# ControlDSP.net
KiCad netlist of a schematic drawn in Altium Designer
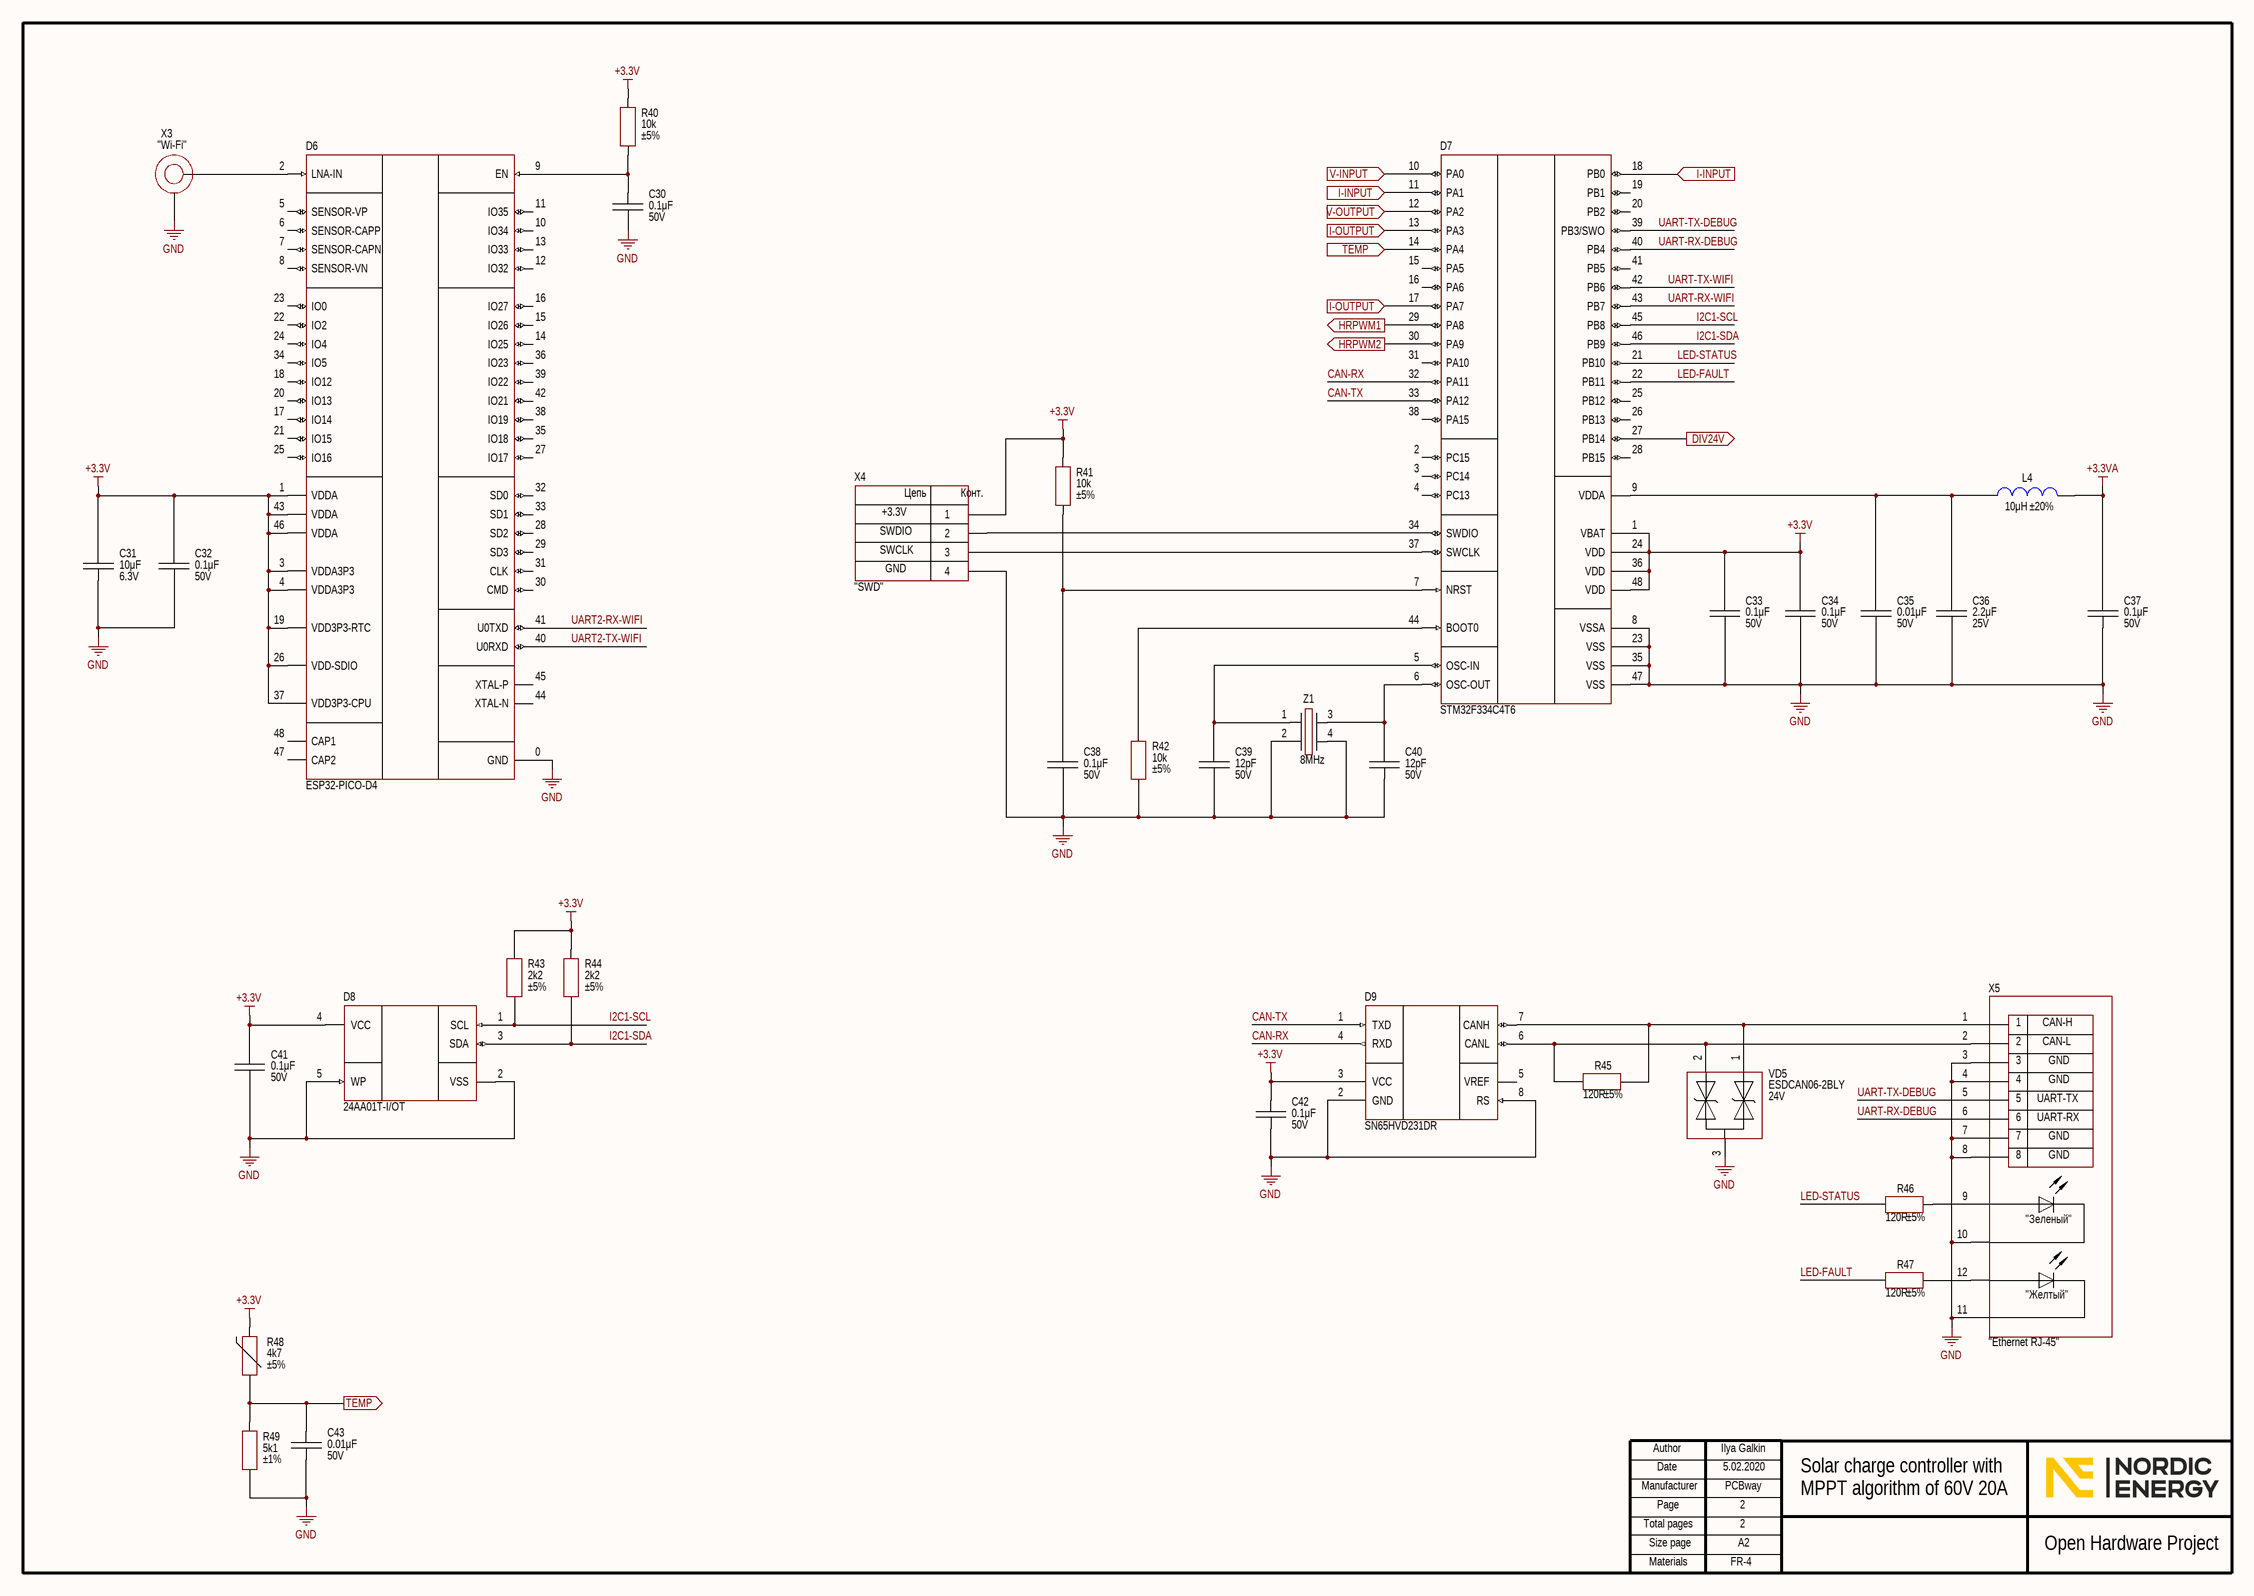
[diagram p0: ControlDSP.SchDoc]

(export (version "E")
  (design (tool "Eeschema 10.0.6"))
  (components
    (comp (ref "C30")
      (value "0.1μF")
      (footprint "CAP: 0805")
      (fields
        (field (name "MANUFACTURER") "Samsung")
        (field (name "PARTNUMBER") "CL21B104KBCNFNC")
        (field (name "VALUEMANUFACTURERPARTNUMBER") "Ceramic capacitor, 0.1μF, X7R, ±10%, 50V, 0805, -55...+125°C")
        (field (name "VOLTAGE") "50V")
      )
      (libsource (lib "Capacitor") (part "Ceramic_0805"))
    )
    (comp (ref "C31")
      (value "10μF")
      (footprint "CAP: 0805")
      (fields
        (field (name "MANUFACTURER") "Samsung")
        (field (name "PARTNUMBER") "CL21B106KQQNNNG")
        (field (name "VALUEMANUFACTURERPARTNUMBER") "Ceramic capacitor, 10μF, X7R, ±10%, 6.3V, 0805, -55...+125°C")
        (field (name "VOLTAGE") "6.3V")
      )
      (libsource (lib "Capacitor") (part "Ceramic_0805"))
    )
    (comp (ref "C32")
      (value "0.1μF")
      (footprint "CAP: 0805")
      (fields
        (field (name "MANUFACTURER") "Samsung")
        (field (name "PARTNUMBER") "CL21B104KBCNFNC")
        (field (name "VALUEMANUFACTURERPARTNUMBER") "Ceramic capacitor, 0.1μF, X7R, ±10%, 50V, 0805, -55...+125°C")
        (field (name "VOLTAGE") "50V")
      )
      (libsource (lib "Capacitor") (part "Ceramic_0805"))
    )
    (comp (ref "C33")
      (value "0.1μF")
      (footprint "CAP: 0805")
      (fields
        (field (name "MANUFACTURER") "Samsung")
        (field (name "PARTNUMBER") "CL21B104KBCNFNC")
        (field (name "VALUEMANUFACTURERPARTNUMBER") "Ceramic capacitor, 0.1μF, X7R, ±10%, 50V, 0805, -55...+125°C")
        (field (name "VOLTAGE") "50V")
      )
      (libsource (lib "Capacitor") (part "Ceramic_0805"))
    )
    (comp (ref "C34")
      (value "0.1μF")
      (footprint "CAP: 0805")
      (fields
        (field (name "MANUFACTURER") "Samsung")
        (field (name "PARTNUMBER") "CL21B104KBCNFNC")
        (field (name "VALUEMANUFACTURERPARTNUMBER") "Ceramic capacitor, 0.1μF, X7R, ±10%, 50V, 0805, -55...+125°C")
        (field (name "VOLTAGE") "50V")
      )
      (libsource (lib "Capacitor") (part "Ceramic_0805"))
    )
    (comp (ref "C35")
      (value "0.01μF")
      (footprint "CAP: 0805")
      (fields
        (field (name "MANUFACTURER") "Samsung")
        (field (name "PARTNUMBER") "CL21B103KBANNNC")
        (field (name "VALUEMANUFACTURERPARTNUMBER") "Ceramic capacitor, 0.01μF, X7R, ±10%, 50V, 0805, -55...+125°C")
        (field (name "VOLTAGE") "50V")
      )
      (libsource (lib "Capacitor") (part "Ceramic_0805"))
    )
    (comp (ref "C36")
      (value "2.2μF")
      (footprint "CAP: 0805")
      (fields
        (field (name "MANUFACTURER") "Samsung")
        (field (name "PARTNUMBER") "CL21B225KAFNFNE")
        (field (name "VALUEMANUFACTURERPARTNUMBER") "Ceramic capacitor, 2.2μF, X7R, ±10%, 25V, 0805, -55...+125°C")
        (field (name "VOLTAGE") "25V")
      )
      (libsource (lib "Capacitor") (part "Ceramic_0805"))
    )
    (comp (ref "C37")
      (value "0.1μF")
      (footprint "CAP: 0805")
      (fields
        (field (name "MANUFACTURER") "Samsung")
        (field (name "PARTNUMBER") "CL21B104KBCNFNC")
        (field (name "VALUEMANUFACTURERPARTNUMBER") "Ceramic capacitor, 0.1μF, X7R, ±10%, 50V, 0805, -55...+125°C")
        (field (name "VOLTAGE") "50V")
      )
      (libsource (lib "Capacitor") (part "Ceramic_0805"))
    )
    (comp (ref "C38")
      (value "0.1μF")
      (footprint "CAP: 0805")
      (fields
        (field (name "MANUFACTURER") "Samsung")
        (field (name "PARTNUMBER") "CL21B104KBCNFNC")
        (field (name "VALUEMANUFACTURERPARTNUMBER") "Ceramic capacitor, 0.1μF, X7R, ±10%, 50V, 0805, -55...+125°C")
        (field (name "VOLTAGE") "50V")
      )
      (libsource (lib "Capacitor") (part "Ceramic_0805"))
    )
    (comp (ref "C39")
      (value "12pF")
      (footprint "CAP: 0805")
      (fields
        (field (name "MANUFACTURER") "Samsung")
        (field (name "PARTNUMBER") "CL21C120JBANNNC")
        (field (name "VALUEMANUFACTURERPARTNUMBER") "Ceramic capacitor, 12pF, NPO, ±5%, 50V, 0805, -55...+125°C")
        (field (name "VOLTAGE") "50V")
      )
      (libsource (lib "Capacitor") (part "Ceramic_0805"))
    )
    (comp (ref "C40")
      (value "12pF")
      (footprint "CAP: 0805")
      (fields
        (field (name "MANUFACTURER") "Samsung")
        (field (name "PARTNUMBER") "CL21C120JBANNNC")
        (field (name "VALUEMANUFACTURERPARTNUMBER") "Ceramic capacitor, 12pF, NPO, ±5%, 50V, 0805, -55...+125°C")
        (field (name "VOLTAGE") "50V")
      )
      (libsource (lib "Capacitor") (part "Ceramic_0805"))
    )
    (comp (ref "C41")
      (value "0.1μF")
      (footprint "CAP: 0805")
      (fields
        (field (name "MANUFACTURER") "Samsung")
        (field (name "PARTNUMBER") "CL21B104KBCNFNC")
        (field (name "VALUEMANUFACTURERPARTNUMBER") "Ceramic capacitor, 0.1μF, X7R, ±10%, 50V, 0805, -55...+125°C")
        (field (name "VOLTAGE") "50V")
      )
      (libsource (lib "Capacitor") (part "Ceramic_0805"))
    )
    (comp (ref "C42")
      (value "0.1μF")
      (footprint "CAP: 0805")
      (fields
        (field (name "MANUFACTURER") "Samsung")
        (field (name "PARTNUMBER") "CL21B104KBCNFNC")
        (field (name "VALUEMANUFACTURERPARTNUMBER") "Ceramic capacitor, 0.1μF, X7R, ±10%, 50V, 0805, -55...+125°C")
        (field (name "VOLTAGE") "50V")
      )
      (libsource (lib "Capacitor") (part "Ceramic_0805"))
    )
    (comp (ref "C43")
      (value "0.01μF")
      (footprint "CAP: 0805")
      (fields
        (field (name "MANUFACTURER") "Samsung")
        (field (name "PARTNUMBER") "CL21B103KBANNNC")
        (field (name "VALUEMANUFACTURERPARTNUMBER") "Ceramic capacitor, 0.01μF, X7R, ±10%, 50V, 0805, -55...+125°C")
        (field (name "VOLTAGE") "50V")
      )
      (libsource (lib "Capacitor") (part "Ceramic_0805"))
    )
    (comp (ref "D6")
      (value "~")
      (footprint "48-LGA (7x7)")
      (description "Wi-Fi+BT")
      (fields (field (name "MANUFACTURER") "Espressif Systems") (field (name "PARTNUMBER") "ESP32-PICO-D4"))
      (libsource (lib "IC. RF transceiver") (part "ESP32-PICO-D4"))
    )
    (comp (ref "D7")
      (value "~")
      (footprint "48-LQFP")
      (description "Cortex-M4")
      (fields
        (field (name "MANUFACTURER") "STMicroelectronics")
        (field (name "VALUEMANUFACTURERPARTNUMBER") "IC microcontroller, 32-Bit, Cortex-M4, 72MHz, 16KB, 12KB, 2...3.6V, -40...+85°C, 48-LQFP")
        (field (name "PARTNUMBER") "STM32F334C4T6")
      )
      (libsource (lib "IC. MCU") (part "STM32F334C4T6"))
    )
    (comp (ref "D8")
      (value "~")
      (footprint "SOT23-5")
      (description "EEPROM")
      (fields
        (field (name "MANUFACTURER") "Microchip Technology")
        (field (name "VALUEMANUFACTURERPARTNUMBER") "IC memory, EEPROM, 1KB (128x8), 400 kHz, I2C, 1.7...5.5V, -40...+85°C, SOT-23-5")
        (field (name "PARTNUMBER") "24AA01T-I/OT")
      )
      (libsource (lib "IC. Memory") (part "24AA01T"))
    )
    (comp (ref "D9")
      (value "~")
      (footprint "8-SOIC")
      (description "CAN")
      (fields
        (field (name "MANUFACTURER") "Texas Instruments")
        (field (name "VALUEMANUFACTURERPARTNUMBER") "IC CAN transceiver, 1Mbps, Half-duplex, 3...3.6V, -40...+85°C, 8-SOIC")
        (field (name "PARTNUMBER") "SN65HVD231DR")
      )
      (libsource (lib "IC. Interface") (part "SN65HVD231DR"))
    )
    (comp (ref "L4")
      (value "10μH")
      (footprint "IND: 0805")
      (fields
        (field (name "MANUFACTURER") "Murata Electronics")
        (field (name "PARTNUMBER") "LQM21DH100M70L")
        (field (name "VALUEMANUFACTURERPARTNUMBER") "Fixed inductor, 10μH, ±20%, 0805, 250mA, -55...+125°C")
        (field (name "TOLERANCE") "±20%")
      )
      (libsource (lib "Inductor") (part "Inductor_0805"))
    )
    (comp (ref "R40")
      (value "10k")
      (footprint "RES: 0805")
      (fields
        (field (name "MANUFACTURER") "Yageo")
        (field (name "PARTNUMBER") "RC0805JR-0710KL")
        (field (name "VALUEMANUFACTURERPARTNUMBER") "Resistor film, 10k, ±5%, 0805, 0.125W, -55...+125°C")
        (field (name "TOLERANCE") "±5%")
      )
      (libsource (lib "") (part "Resistor_0805_1"))
    )
    (comp (ref "R41")
      (value "10k")
      (footprint "RES: 0805")
      (fields
        (field (name "MANUFACTURER") "Yageo")
        (field (name "PARTNUMBER") "RC0805JR-0710KL")
        (field (name "VALUEMANUFACTURERPARTNUMBER") "Resistor film, 10k, ±5%, 0805, 0.125W, -55...+125°C")
        (field (name "TOLERANCE") "±5%")
      )
      (libsource (lib "") (part "Resistor_0805_1"))
    )
    (comp (ref "R42")
      (value "10k")
      (footprint "RES: 0805")
      (fields
        (field (name "MANUFACTURER") "Yageo")
        (field (name "PARTNUMBER") "RC0805JR-0710KL")
        (field (name "VALUEMANUFACTURERPARTNUMBER") "Resistor film, 10k, ±5%, 0805, 0.125W, -55...+125°C")
        (field (name "TOLERANCE") "±5%")
      )
      (libsource (lib "") (part "Resistor_0805_1"))
    )
    (comp (ref "R43")
      (value "2k2")
      (footprint "RES: 0805")
      (fields
        (field (name "MANUFACTURER") "Yageo")
        (field (name "PARTNUMBER") "RC0805JR-072K2L")
        (field (name "VALUEMANUFACTURERPARTNUMBER") "Resistor film, 2k2, ±5%, 0805, 0.125W, -55...+125°C")
        (field (name "TOLERANCE") "±5%")
      )
      (libsource (lib "") (part "Resistor_0805_1"))
    )
    (comp (ref "R44")
      (value "2k2")
      (footprint "RES: 0805")
      (fields
        (field (name "MANUFACTURER") "Yageo")
        (field (name "PARTNUMBER") "RC0805JR-072K2L")
        (field (name "VALUEMANUFACTURERPARTNUMBER") "Resistor film, 2k2, ±5%, 0805, 0.125W, -55...+125°C")
        (field (name "TOLERANCE") "±5%")
      )
      (libsource (lib "") (part "Resistor_0805_1"))
    )
    (comp (ref "R45")
      (value "120R")
      (footprint "RES: 0805")
      (fields
        (field (name "MANUFACTURER") "Yageo")
        (field (name "PARTNUMBER") "RC0805JR-07120RL")
        (field (name "VALUEMANUFACTURERPARTNUMBER") "Resistor film, 120R, ±5%, 0805, 0.125W, -55...+125°C")
        (field (name "TOLERANCE") "±5%")
      )
      (libsource (lib "Resistor") (part "Resistor_0805"))
    )
    (comp (ref "R46")
      (value "120R")
      (footprint "RES: 0805")
      (fields
        (field (name "MANUFACTURER") "Yageo")
        (field (name "PARTNUMBER") "RC0805JR-07120RL")
        (field (name "VALUEMANUFACTURERPARTNUMBER") "Resistor film, 120R, ±5%, 0805, 0.125W, -55...+125°C")
        (field (name "TOLERANCE") "±5%")
      )
      (libsource (lib "Resistor") (part "Resistor_0805"))
    )
    (comp (ref "R47")
      (value "120R")
      (footprint "RES: 0805")
      (fields
        (field (name "MANUFACTURER") "Yageo")
        (field (name "PARTNUMBER") "RC0805JR-07120RL")
        (field (name "VALUEMANUFACTURERPARTNUMBER") "Resistor film, 120R, ±5%, 0805, 0.125W, -55...+125°C")
        (field (name "TOLERANCE") "±5%")
      )
      (libsource (lib "Resistor") (part "Resistor_0805"))
    )
    (comp (ref "R48")
      (value "4k7")
      (footprint "RES: 0805")
      (fields
        (field (name "MANUFACTURER") "TDK")
        (field (name "PARTNUMBER") "B57401V2472J062")
        (field (name "VALUEMANUFACTURERPARTNUMBER") "NTC resistor, 4k7, ±5%, 0805, 3650K, -55...+125°C")
        (field (name "TOLERANCE") "±5%")
      )
      (libsource (lib "Resistor") (part "NTC"))
    )
    (comp (ref "R49")
      (value "5k1")
      (footprint "RES: 0805")
      (fields
        (field (name "MANUFACTURER") "Yageo")
        (field (name "PARTNUMBER") "RC0805FR-075K1L")
        (field (name "VALUEMANUFACTURERPARTNUMBER") "Resistor film, 5k1, ±1%, 0805, 0.125W, -55...+125°C")
        (field (name "TOLERANCE") "±1%")
      )
      (libsource (lib "") (part "Resistor_0805_1"))
    )
    (comp (ref "VD5")
      (value "~")
      (footprint "SOT23")
      (fields
        (field (name "MANUFACTURER") "STMicroelectronics")
        (field (name "VALUEMANUFACTURERPARTNUMBER") "TVS diode, 24V, 230W peak, 3A, 13pF, SOT-23, -40...+150°C")
        (field (name "VOLTAGE") "24V")
        (field (name "PARTNUMBER") "ESDCAN06-2BLY")
      )
      (libsource (lib "Diode") (part "TVS_array"))
    )
    (comp (ref "X3")
      (value "~")
      (footprint "CON: u.Fl")
      (fields
        (field (name "MANUFACTURER") "Hirose Electric")
        (field (name "VALUEMANUFACTURERPARTNUMBER") "Connector u.FL, 50 Ohm, 6GHz")
        (field (name "PARTNUMBER") "U.FL-R-SMT(01)")
        (field (name "COMMENTTEXT") "\"Wi-Fi\"")
      )
      (libsource (lib "Connector") (part "Connector_uFL"))
    )
    (comp (ref "X4")
      (value "~")
      (footprint "CON: SM04B-GHS")
      (fields
        (field (name "MANUFACTURER") "JST")
        (field (name "VALUEMANUFACTURERPARTNUMBER") "Connector, 4pin, 1.25mm, 50VDC, 1A")
        (field (name "PARTNUMBER") "SM04B-GHS")
        (field (name "COMMENTTEXT") "\"SWD\"")
      )
      (libsource (lib "Connector") (part "Connector_SM04B"))
    )
    (comp (ref "X5")
      (value "~")
      (footprint "CON: RJ-45 (615008137421 / DS1128-09-S8B8S)")
      (fields
        (field (name "MANUFACTURER") "Wurth")
        (field (name "VALUEMANUFACTURERPARTNUMBER") "Etherner RJ-45 connector")
        (field (name "PARTNUMBER") "615008137421")
        (field (name "COMMENTTEXT") "\"Ethernet RJ-45\"")
      )
      (libsource (lib "Connector") (part "Connector_RJ45"))
    )
    (comp (ref "Z1")
      (value "~")
      (footprint "OSC: 3225")
      (fields
        (field (name "MANUFACTURER") "ECS")
        (field (name "PARTNUMBER") "ECS-80-12-33-JGN-TR")
        (field (name "VALUEMANUFACTURERPARTNUMBER") "Crystal, 8MHz, 12pF, ±30ppm, case 3225, -40...+85°C")
        (field (name "FREQUENCY") "8MHz")
      )
      (libsource (lib "Oscilator") (part "Crystal_3225"))
    )
  )
  (nets
    (net (code "1") (name "+3.3V") (class "Default")
      (node (ref "C31") (pin "2") (pinfunction "2_2") (pintype "power_in"))
      (node (ref "C32") (pin "2") (pinfunction "2_2") (pintype "power_in"))
      (node (ref "C33") (pin "2") (pinfunction "2_2") (pintype "power_in"))
      (node (ref "C34") (pin "2") (pinfunction "2_2") (pintype "power_in"))
      (node (ref "C41") (pin "2") (pinfunction "2_2") (pintype "power_in"))
      (node (ref "C42") (pin "2") (pinfunction "2_2") (pintype "power_in"))
      (node (ref "D6") (pin "1") (pinfunction "VDDA_1") (pintype "passive"))
      (node (ref "D6") (pin "19") (pinfunction "VDD3P3-RTC_19") (pintype "passive"))
      (node (ref "D6") (pin "26") (pinfunction "VDD-SDIO_26") (pintype "passive"))
      (node (ref "D6") (pin "3") (pinfunction "VDDA3P3_3") (pintype "passive"))
      (node (ref "D6") (pin "37") (pinfunction "VDD3P3-CPU_37") (pintype "passive"))
      (node (ref "D6") (pin "4") (pinfunction "VDDA3P3_4") (pintype "passive"))
      (node (ref "D6") (pin "43") (pinfunction "VDDA_43") (pintype "passive"))
      (node (ref "D6") (pin "46") (pinfunction "VDDA_46") (pintype "passive"))
      (node (ref "D7") (pin "1") (pinfunction "VBAT_1") (pintype "passive"))
      (node (ref "D7") (pin "24") (pinfunction "VDD_24") (pintype "passive"))
      (node (ref "D7") (pin "36") (pinfunction "VDD_36") (pintype "passive"))
      (node (ref "D7") (pin "48") (pinfunction "VDD_48") (pintype "passive"))
      (node (ref "D8") (pin "4") (pinfunction "VCC_4") (pintype "power_in"))
      (node (ref "D9") (pin "3") (pinfunction "VCC_3") (pintype "passive"))
      (node (ref "R40") (pin "2") (pinfunction "2_2") (pintype "passive"))
      (node (ref "R41") (pin "2") (pinfunction "2_2") (pintype "passive"))
      (node (ref "R43") (pin "2") (pinfunction "2_2") (pintype "passive"))
      (node (ref "R44") (pin "2") (pinfunction "2_2") (pintype "passive"))
      (node (ref "R48") (pin "2") (pinfunction "2_2") (pintype "passive"))
      (node (ref "X4") (pin "1") (pinfunction "1_1") (pintype "passive"))
    )
    (net (code "2") (name "+3.3VA") (class "Default")
      (node (ref "C37") (pin "2") (pinfunction "2_2") (pintype "power_in"))
      (node (ref "L4") (pin "1") (pinfunction "1_1") (pintype "passive"))
    )
    (net (code "3") (name "/CAN-RX") (class "Default")
      (node (ref "D7") (pin "32") (pinfunction "PA11_32") (pintype "bidirectional"))
      (node (ref "D9") (pin "4") (pinfunction "RXD_4") (pintype "output"))
    )
    (net (code "4") (name "/CAN-TX") (class "Default")
      (node (ref "D7") (pin "33") (pinfunction "PA12_33") (pintype "bidirectional"))
      (node (ref "D9") (pin "1") (pinfunction "TXD_1") (pintype "input"))
    )
    (net (code "5") (name "/DIV24V") (class "Default")
      (node (ref "D7") (pin "27") (pinfunction "PB14_27") (pintype "bidirectional"))
    )
    (net (code "6") (name "/HRPWM1") (class "Default")
      (node (ref "D7") (pin "29") (pinfunction "PA8_29") (pintype "bidirectional"))
    )
    (net (code "7") (name "/HRPWM2") (class "Default")
      (node (ref "D7") (pin "30") (pinfunction "PA9_30") (pintype "bidirectional"))
    )
    (net (code "8") (name "/I-INPUT") (class "Default")
      (node (ref "D7") (pin "11") (pinfunction "PA1_11") (pintype "bidirectional"))
      (node (ref "D7") (pin "18") (pinfunction "PB0_18") (pintype "bidirectional"))
    )
    (net (code "9") (name "/I-OUTPUT") (class "Default")
      (node (ref "D7") (pin "13") (pinfunction "PA3_13") (pintype "bidirectional"))
      (node (ref "D7") (pin "17") (pinfunction "PA7_17") (pintype "bidirectional"))
    )
    (net (code "10") (name "/I2C1-SCL") (class "Default")
      (node (ref "D7") (pin "45") (pinfunction "PB8_45") (pintype "bidirectional"))
      (node (ref "D8") (pin "1") (pinfunction "SCL_1") (pintype "input"))
      (node (ref "R43") (pin "1") (pinfunction "1_1") (pintype "passive"))
    )
    (net (code "11") (name "/I2C1-SDA") (class "Default")
      (node (ref "D7") (pin "46") (pinfunction "PB9_46") (pintype "bidirectional"))
      (node (ref "D8") (pin "3") (pinfunction "SDA_3") (pintype "bidirectional"))
      (node (ref "R44") (pin "1") (pinfunction "1_1") (pintype "passive"))
    )
    (net (code "12") (name "/LED-FAULT") (class "Default")
      (node (ref "D7") (pin "22") (pinfunction "PB11_22") (pintype "bidirectional"))
      (node (ref "R47") (pin "2") (pinfunction "2_2") (pintype "passive"))
    )
    (net (code "13") (name "/LED-STATUS") (class "Default")
      (node (ref "D7") (pin "21") (pinfunction "PB10_21") (pintype "bidirectional"))
      (node (ref "R46") (pin "2") (pinfunction "2_2") (pintype "passive"))
    )
    (net (code "14") (name "/TEMP") (class "Default")
      (node (ref "C43") (pin "2") (pinfunction "2_2") (pintype "power_in"))
      (node (ref "D7") (pin "14") (pinfunction "PA4_14") (pintype "bidirectional"))
      (node (ref "R48") (pin "1") (pinfunction "1_1") (pintype "passive"))
      (node (ref "R49") (pin "2") (pinfunction "2_2") (pintype "passive"))
    )
    (net (code "15") (name "/UART-RX-DEBUG") (class "Default")
      (node (ref "D7") (pin "40") (pinfunction "PB4_40") (pintype "bidirectional"))
      (node (ref "X5") (pin "6") (pinfunction "D2_6") (pintype "passive"))
    )
    (net (code "16") (name "/UART-RX-WIFI") (class "Default")
      (node (ref "D7") (pin "43") (pinfunction "PB7_43") (pintype "bidirectional"))
    )
    (net (code "17") (name "/UART-TX-DEBUG") (class "Default")
      (node (ref "D7") (pin "39") (pinfunction "PB3/SWO_39") (pintype "bidirectional"))
      (node (ref "X5") (pin "5") (pinfunction "D2_5") (pintype "passive"))
    )
    (net (code "18") (name "/UART-TX-WIFI") (class "Default")
      (node (ref "D7") (pin "42") (pinfunction "PB6_42") (pintype "bidirectional"))
    )
    (net (code "19") (name "/UART2-RX-WIFI") (class "Default")
      (node (ref "D6") (pin "41") (pinfunction "U0TXD_41") (pintype "bidirectional"))
    )
    (net (code "20") (name "/UART2-TX-WIFI") (class "Default")
      (node (ref "D6") (pin "40") (pinfunction "U0RXD_40") (pintype "bidirectional"))
    )
    (net (code "21") (name "/V-INPUT") (class "Default")
      (node (ref "D7") (pin "10") (pinfunction "PA0_10") (pintype "bidirectional"))
    )
    (net (code "22") (name "/V-OUTPUT") (class "Default")
      (node (ref "D7") (pin "12") (pinfunction "PA2_12") (pintype "bidirectional"))
    )
    (net (code "23") (name "GND") (class "Default")
      (node (ref "C30") (pin "1") (pinfunction "1_1") (pintype "power_in"))
      (node (ref "C31") (pin "1") (pinfunction "1_1") (pintype "power_in"))
      (node (ref "C32") (pin "1") (pinfunction "1_1") (pintype "power_in"))
      (node (ref "C33") (pin "1") (pinfunction "1_1") (pintype "power_in"))
      (node (ref "C34") (pin "1") (pinfunction "1_1") (pintype "power_in"))
      (node (ref "C35") (pin "1") (pinfunction "1_1") (pintype "power_in"))
      (node (ref "C36") (pin "1") (pinfunction "1_1") (pintype "power_in"))
      (node (ref "C37") (pin "1") (pinfunction "1_1") (pintype "power_in"))
      (node (ref "C38") (pin "1") (pinfunction "1_1") (pintype "power_in"))
      (node (ref "C39") (pin "1") (pinfunction "1_1") (pintype "power_in"))
      (node (ref "C40") (pin "1") (pinfunction "1_1") (pintype "power_in"))
      (node (ref "C41") (pin "1") (pinfunction "1_1") (pintype "power_in"))
      (node (ref "C42") (pin "1") (pinfunction "1_1") (pintype "power_in"))
      (node (ref "C43") (pin "1") (pinfunction "1_1") (pintype "power_in"))
      (node (ref "D6") (pin "0") (pinfunction "GND_0") (pintype "passive"))
      (node (ref "D7") (pin "23") (pinfunction "VSS_23") (pintype "passive"))
      (node (ref "D7") (pin "35") (pinfunction "VSS_35") (pintype "passive"))
      (node (ref "D7") (pin "47") (pinfunction "VSS_47") (pintype "passive"))
      (node (ref "D7") (pin "8") (pinfunction "VSSA_8") (pintype "passive"))
      (node (ref "D8") (pin "2") (pinfunction "VSS_2") (pintype "power_in"))
      (node (ref "D8") (pin "5") (pinfunction "WP_5") (pintype "input"))
      (node (ref "D9") (pin "2") (pinfunction "GND_2") (pintype "passive"))
      (node (ref "D9") (pin "8") (pinfunction "RS_8") (pintype "input"))
      (node (ref "R42") (pin "1") (pinfunction "1_1") (pintype "passive"))
      (node (ref "R49") (pin "1") (pinfunction "1_1") (pintype "passive"))
      (node (ref "VD5") (pin "3") (pintype "passive"))
      (node (ref "X3") (pin "2") (pinfunction "2_2") (pintype "passive"))
      (node (ref "X4") (pin "4") (pinfunction "4_4") (pintype "power_in"))
      (node (ref "X5") (pin "10") (pinfunction "D1_10") (pintype "passive"))
      (node (ref "X5") (pin "11") (pinfunction "D3_11") (pintype "passive"))
      (node (ref "X5") (pin "3") (pinfunction "D2_3") (pintype "passive"))
      (node (ref "X5") (pin "4") (pinfunction "D2_4") (pintype "passive"))
      (node (ref "X5") (pin "7") (pinfunction "D2_7") (pintype "passive"))
      (node (ref "X5") (pin "8") (pinfunction "D2_8") (pintype "passive"))
      (node (ref "Z1") (pin "2") (pinfunction "2_2") (pintype "passive"))
      (node (ref "Z1") (pin "4") (pinfunction "4_4") (pintype "passive"))
    )
    (net (code "24") (name "Net-(D6-EN)") (class "Default")
      (node (ref "C30") (pin "2") (pinfunction "2_2") (pintype "power_in"))
      (node (ref "D6") (pin "9") (pinfunction "EN_9") (pintype "input"))
      (node (ref "R40") (pin "1") (pinfunction "1_1") (pintype "passive"))
    )
    (net (code "25") (name "Net-(D6-LNA-IN)") (class "Default")
      (node (ref "D6") (pin "2") (pinfunction "LNA-IN_2") (pintype "input"))
      (node (ref "X3") (pin "1") (pinfunction "1_1") (pintype "passive"))
    )
    (net (code "26") (name "Net-(D7-BOOT0)") (class "Default")
      (node (ref "D7") (pin "44") (pinfunction "BOOT0_44") (pintype "input"))
      (node (ref "R42") (pin "2") (pinfunction "2_2") (pintype "passive"))
    )
    (net (code "27") (name "Net-(D7-NRST)") (class "Default")
      (node (ref "C38") (pin "2") (pinfunction "2_2") (pintype "power_in"))
      (node (ref "D7") (pin "7") (pinfunction "NRST_7") (pintype "input"))
      (node (ref "R41") (pin "1") (pinfunction "1_1") (pintype "passive"))
    )
    (net (code "28") (name "Net-(D7-OSC-IN)") (class "Default")
      (node (ref "C39") (pin "2") (pinfunction "2_2") (pintype "power_in"))
      (node (ref "D7") (pin "5") (pinfunction "OSC-IN_5") (pintype "bidirectional"))
      (node (ref "Z1") (pin "1") (pinfunction "1_1") (pintype "passive"))
    )
    (net (code "29") (name "Net-(D7-OSC-OUT)") (class "Default")
      (node (ref "C40") (pin "2") (pinfunction "2_2") (pintype "power_in"))
      (node (ref "D7") (pin "6") (pinfunction "OSC-OUT_6") (pintype "bidirectional"))
      (node (ref "Z1") (pin "3") (pinfunction "3_3") (pintype "passive"))
    )
    (net (code "30") (name "Net-(D7-SWCLK)") (class "Default")
      (node (ref "D7") (pin "37") (pinfunction "SWCLK_37") (pintype "bidirectional"))
      (node (ref "X4") (pin "3") (pinfunction "3_3") (pintype "power_in"))
    )
    (net (code "31") (name "Net-(D7-SWDIO)") (class "Default")
      (node (ref "D7") (pin "34") (pinfunction "SWDIO_34") (pintype "bidirectional"))
      (node (ref "X4") (pin "2") (pinfunction "2_2") (pintype "passive"))
    )
    (net (code "32") (name "Net-(D7-VDDA)") (class "Default")
      (node (ref "C35") (pin "2") (pinfunction "2_2") (pintype "power_in"))
      (node (ref "C36") (pin "2") (pinfunction "2_2") (pintype "power_in"))
      (node (ref "D7") (pin "9") (pinfunction "VDDA_9") (pintype "passive"))
      (node (ref "L4") (pin "2") (pinfunction "2_2") (pintype "passive"))
    )
    (net (code "33") (name "Net-(D9-CANH)") (class "Default")
      (node (ref "D9") (pin "7") (pinfunction "CANH_7") (pintype "bidirectional"))
      (node (ref "R45") (pin "1") (pinfunction "1_1") (pintype "passive"))
      (node (ref "VD5") (pin "1") (pintype "passive"))
      (node (ref "X5") (pin "1") (pinfunction "D2_1") (pintype "passive"))
    )
    (net (code "34") (name "Net-(D9-CANL)") (class "Default")
      (node (ref "D9") (pin "6") (pinfunction "CANL_6") (pintype "bidirectional"))
      (node (ref "R45") (pin "2") (pinfunction "2_2") (pintype "passive"))
      (node (ref "VD5") (pin "2") (pintype "passive"))
      (node (ref "X5") (pin "2") (pinfunction "D2_2") (pintype "passive"))
    )
    (net (code "35") (name "Net-(R46-Pad1)") (class "Default")
      (node (ref "R46") (pin "1") (pinfunction "1_1") (pintype "passive"))
      (node (ref "X5") (pin "9") (pinfunction "D2_9") (pintype "passive"))
    )
    (net (code "36") (name "Net-(X5-D4)") (class "Default")
      (node (ref "R47") (pin "1") (pinfunction "1_1") (pintype "passive"))
      (node (ref "X5") (pin "12") (pinfunction "D4_12") (pintype "passive"))
    )
    (net (code "37") (name "unconnected-(D6-CAP1-Pad48)") (class "Default")
      (node (ref "D6") (pin "48") (pinfunction "CAP1_48") (pintype "passive"))
    )
    (net (code "38") (name "unconnected-(D6-CAP2-Pad47)") (class "Default")
      (node (ref "D6") (pin "47") (pinfunction "CAP2_47") (pintype "passive"))
    )
    (net (code "39") (name "unconnected-(D6-CLK-Pad31)") (class "Default")
      (node (ref "D6") (pin "31") (pinfunction "CLK_31") (pintype "bidirectional"))
    )
    (net (code "40") (name "unconnected-(D6-CMD-Pad30)") (class "Default")
      (node (ref "D6") (pin "30") (pinfunction "CMD_30") (pintype "bidirectional"))
    )
    (net (code "41") (name "unconnected-(D6-IO0-Pad23)") (class "Default")
      (node (ref "D6") (pin "23") (pinfunction "IO0_23") (pintype "bidirectional"))
    )
    (net (code "42") (name "unconnected-(D6-IO2-Pad22)") (class "Default")
      (node (ref "D6") (pin "22") (pinfunction "IO2_22") (pintype "bidirectional"))
    )
    (net (code "43") (name "unconnected-(D6-IO4-Pad24)") (class "Default")
      (node (ref "D6") (pin "24") (pinfunction "IO4_24") (pintype "bidirectional"))
    )
    (net (code "44") (name "unconnected-(D6-IO5-Pad34)") (class "Default")
      (node (ref "D6") (pin "34") (pinfunction "IO5_34") (pintype "bidirectional"))
    )
    (net (code "45") (name "unconnected-(D6-IO12-Pad18)") (class "Default")
      (node (ref "D6") (pin "18") (pinfunction "IO12_18") (pintype "bidirectional"))
    )
    (net (code "46") (name "unconnected-(D6-IO13-Pad20)") (class "Default")
      (node (ref "D6") (pin "20") (pinfunction "IO13_20") (pintype "bidirectional"))
    )
    (net (code "47") (name "unconnected-(D6-IO14-Pad17)") (class "Default")
      (node (ref "D6") (pin "17") (pinfunction "IO14_17") (pintype "bidirectional"))
    )
    (net (code "48") (name "unconnected-(D6-IO15-Pad21)") (class "Default")
      (node (ref "D6") (pin "21") (pinfunction "IO15_21") (pintype "bidirectional"))
    )
    (net (code "49") (name "unconnected-(D6-IO16-Pad25)") (class "Default")
      (node (ref "D6") (pin "25") (pinfunction "IO16_25") (pintype "bidirectional"))
    )
    (net (code "50") (name "unconnected-(D6-IO17-Pad27)") (class "Default")
      (node (ref "D6") (pin "27") (pinfunction "IO17_27") (pintype "bidirectional"))
    )
    (net (code "51") (name "unconnected-(D6-IO18-Pad35)") (class "Default")
      (node (ref "D6") (pin "35") (pinfunction "IO18_35") (pintype "bidirectional"))
    )
    (net (code "52") (name "unconnected-(D6-IO19-Pad38)") (class "Default")
      (node (ref "D6") (pin "38") (pinfunction "IO19_38") (pintype "bidirectional"))
    )
    (net (code "53") (name "unconnected-(D6-IO21-Pad42)") (class "Default")
      (node (ref "D6") (pin "42") (pinfunction "IO21_42") (pintype "bidirectional"))
    )
    (net (code "54") (name "unconnected-(D6-IO22-Pad39)") (class "Default")
      (node (ref "D6") (pin "39") (pinfunction "IO22_39") (pintype "bidirectional"))
    )
    (net (code "55") (name "unconnected-(D6-IO23-Pad36)") (class "Default")
      (node (ref "D6") (pin "36") (pinfunction "IO23_36") (pintype "bidirectional"))
    )
    (net (code "56") (name "unconnected-(D6-IO25-Pad14)") (class "Default")
      (node (ref "D6") (pin "14") (pinfunction "IO25_14") (pintype "bidirectional"))
    )
    (net (code "57") (name "unconnected-(D6-IO26-Pad15)") (class "Default")
      (node (ref "D6") (pin "15") (pinfunction "IO26_15") (pintype "bidirectional"))
    )
    (net (code "58") (name "unconnected-(D6-IO27-Pad16)") (class "Default")
      (node (ref "D6") (pin "16") (pinfunction "IO27_16") (pintype "bidirectional"))
    )
    (net (code "59") (name "unconnected-(D6-IO32-Pad12)") (class "Default")
      (node (ref "D6") (pin "12") (pinfunction "IO32_12") (pintype "bidirectional"))
    )
    (net (code "60") (name "unconnected-(D6-IO33-Pad13)") (class "Default")
      (node (ref "D6") (pin "13") (pinfunction "IO33_13") (pintype "bidirectional"))
    )
    (net (code "61") (name "unconnected-(D6-IO34-Pad10)") (class "Default")
      (node (ref "D6") (pin "10") (pinfunction "IO34_10") (pintype "bidirectional"))
    )
    (net (code "62") (name "unconnected-(D6-IO35-Pad11)") (class "Default")
      (node (ref "D6") (pin "11") (pinfunction "IO35_11") (pintype "bidirectional"))
    )
    (net (code "63") (name "unconnected-(D6-SD0-Pad32)") (class "Default")
      (node (ref "D6") (pin "32") (pinfunction "SD0_32") (pintype "bidirectional"))
    )
    (net (code "64") (name "unconnected-(D6-SD1-Pad33)") (class "Default")
      (node (ref "D6") (pin "33") (pinfunction "SD1_33") (pintype "bidirectional"))
    )
    (net (code "65") (name "unconnected-(D6-SD2-Pad28)") (class "Default")
      (node (ref "D6") (pin "28") (pinfunction "SD2_28") (pintype "bidirectional"))
    )
    (net (code "66") (name "unconnected-(D6-SD3-Pad29)") (class "Default")
      (node (ref "D6") (pin "29") (pinfunction "SD3_29") (pintype "bidirectional"))
    )
    (net (code "67") (name "unconnected-(D6-SENSOR-CAPN-Pad7)") (class "Default")
      (node (ref "D6") (pin "7") (pinfunction "SENSOR-CAPN_7") (pintype "bidirectional"))
    )
    (net (code "68") (name "unconnected-(D6-SENSOR-CAPP-Pad6)") (class "Default")
      (node (ref "D6") (pin "6") (pinfunction "SENSOR-CAPP_6") (pintype "bidirectional"))
    )
    (net (code "69") (name "unconnected-(D6-SENSOR-VN-Pad8)") (class "Default")
      (node (ref "D6") (pin "8") (pinfunction "SENSOR-VN_8") (pintype "bidirectional"))
    )
    (net (code "70") (name "unconnected-(D6-SENSOR-VP-Pad5)") (class "Default")
      (node (ref "D6") (pin "5") (pinfunction "SENSOR-VP_5") (pintype "bidirectional"))
    )
    (net (code "71") (name "unconnected-(D6-XTAL-N-Pad44)") (class "Default")
      (node (ref "D6") (pin "44") (pinfunction "XTAL-N_44") (pintype "passive"))
    )
    (net (code "72") (name "unconnected-(D6-XTAL-P-Pad45)") (class "Default")
      (node (ref "D6") (pin "45") (pinfunction "XTAL-P_45") (pintype "passive"))
    )
    (net (code "73") (name "unconnected-(D7-PA5-Pad15)") (class "Default")
      (node (ref "D7") (pin "15") (pinfunction "PA5_15") (pintype "bidirectional"))
    )
    (net (code "74") (name "unconnected-(D7-PA6-Pad16)") (class "Default")
      (node (ref "D7") (pin "16") (pinfunction "PA6_16") (pintype "bidirectional"))
    )
    (net (code "75") (name "unconnected-(D7-PA10-Pad31)") (class "Default")
      (node (ref "D7") (pin "31") (pinfunction "PA10_31") (pintype "bidirectional"))
    )
    (net (code "76") (name "unconnected-(D7-PA15-Pad38)") (class "Default")
      (node (ref "D7") (pin "38") (pinfunction "PA15_38") (pintype "bidirectional"))
    )
    (net (code "77") (name "unconnected-(D7-PB1-Pad19)") (class "Default")
      (node (ref "D7") (pin "19") (pinfunction "PB1_19") (pintype "bidirectional"))
    )
    (net (code "78") (name "unconnected-(D7-PB2-Pad20)") (class "Default")
      (node (ref "D7") (pin "20") (pinfunction "PB2_20") (pintype "bidirectional"))
    )
    (net (code "79") (name "unconnected-(D7-PB5-Pad41)") (class "Default")
      (node (ref "D7") (pin "41") (pinfunction "PB5_41") (pintype "bidirectional"))
    )
    (net (code "80") (name "unconnected-(D7-PB12-Pad25)") (class "Default")
      (node (ref "D7") (pin "25") (pinfunction "PB12_25") (pintype "bidirectional"))
    )
    (net (code "81") (name "unconnected-(D7-PB13-Pad26)") (class "Default")
      (node (ref "D7") (pin "26") (pinfunction "PB13_26") (pintype "bidirectional"))
    )
    (net (code "82") (name "unconnected-(D7-PB15-Pad28)") (class "Default")
      (node (ref "D7") (pin "28") (pinfunction "PB15_28") (pintype "bidirectional"))
    )
    (net (code "83") (name "unconnected-(D7-PC13-Pad4)") (class "Default")
      (node (ref "D7") (pin "4") (pinfunction "PC13_4") (pintype "bidirectional"))
    )
    (net (code "84") (name "unconnected-(D7-PC14-Pad3)") (class "Default")
      (node (ref "D7") (pin "3") (pinfunction "PC14_3") (pintype "bidirectional"))
    )
    (net (code "85") (name "unconnected-(D7-PC15-Pad2)") (class "Default")
      (node (ref "D7") (pin "2") (pinfunction "PC15_2") (pintype "bidirectional"))
    )
    (net (code "86") (name "unconnected-(D9-VREF-Pad5)") (class "Default")
      (node (ref "D9") (pin "5") (pinfunction "VREF_5") (pintype "passive"))
    )
  )
)
